# imu_hand.net
KiCad netlist of a schematic drawn in EAGLE
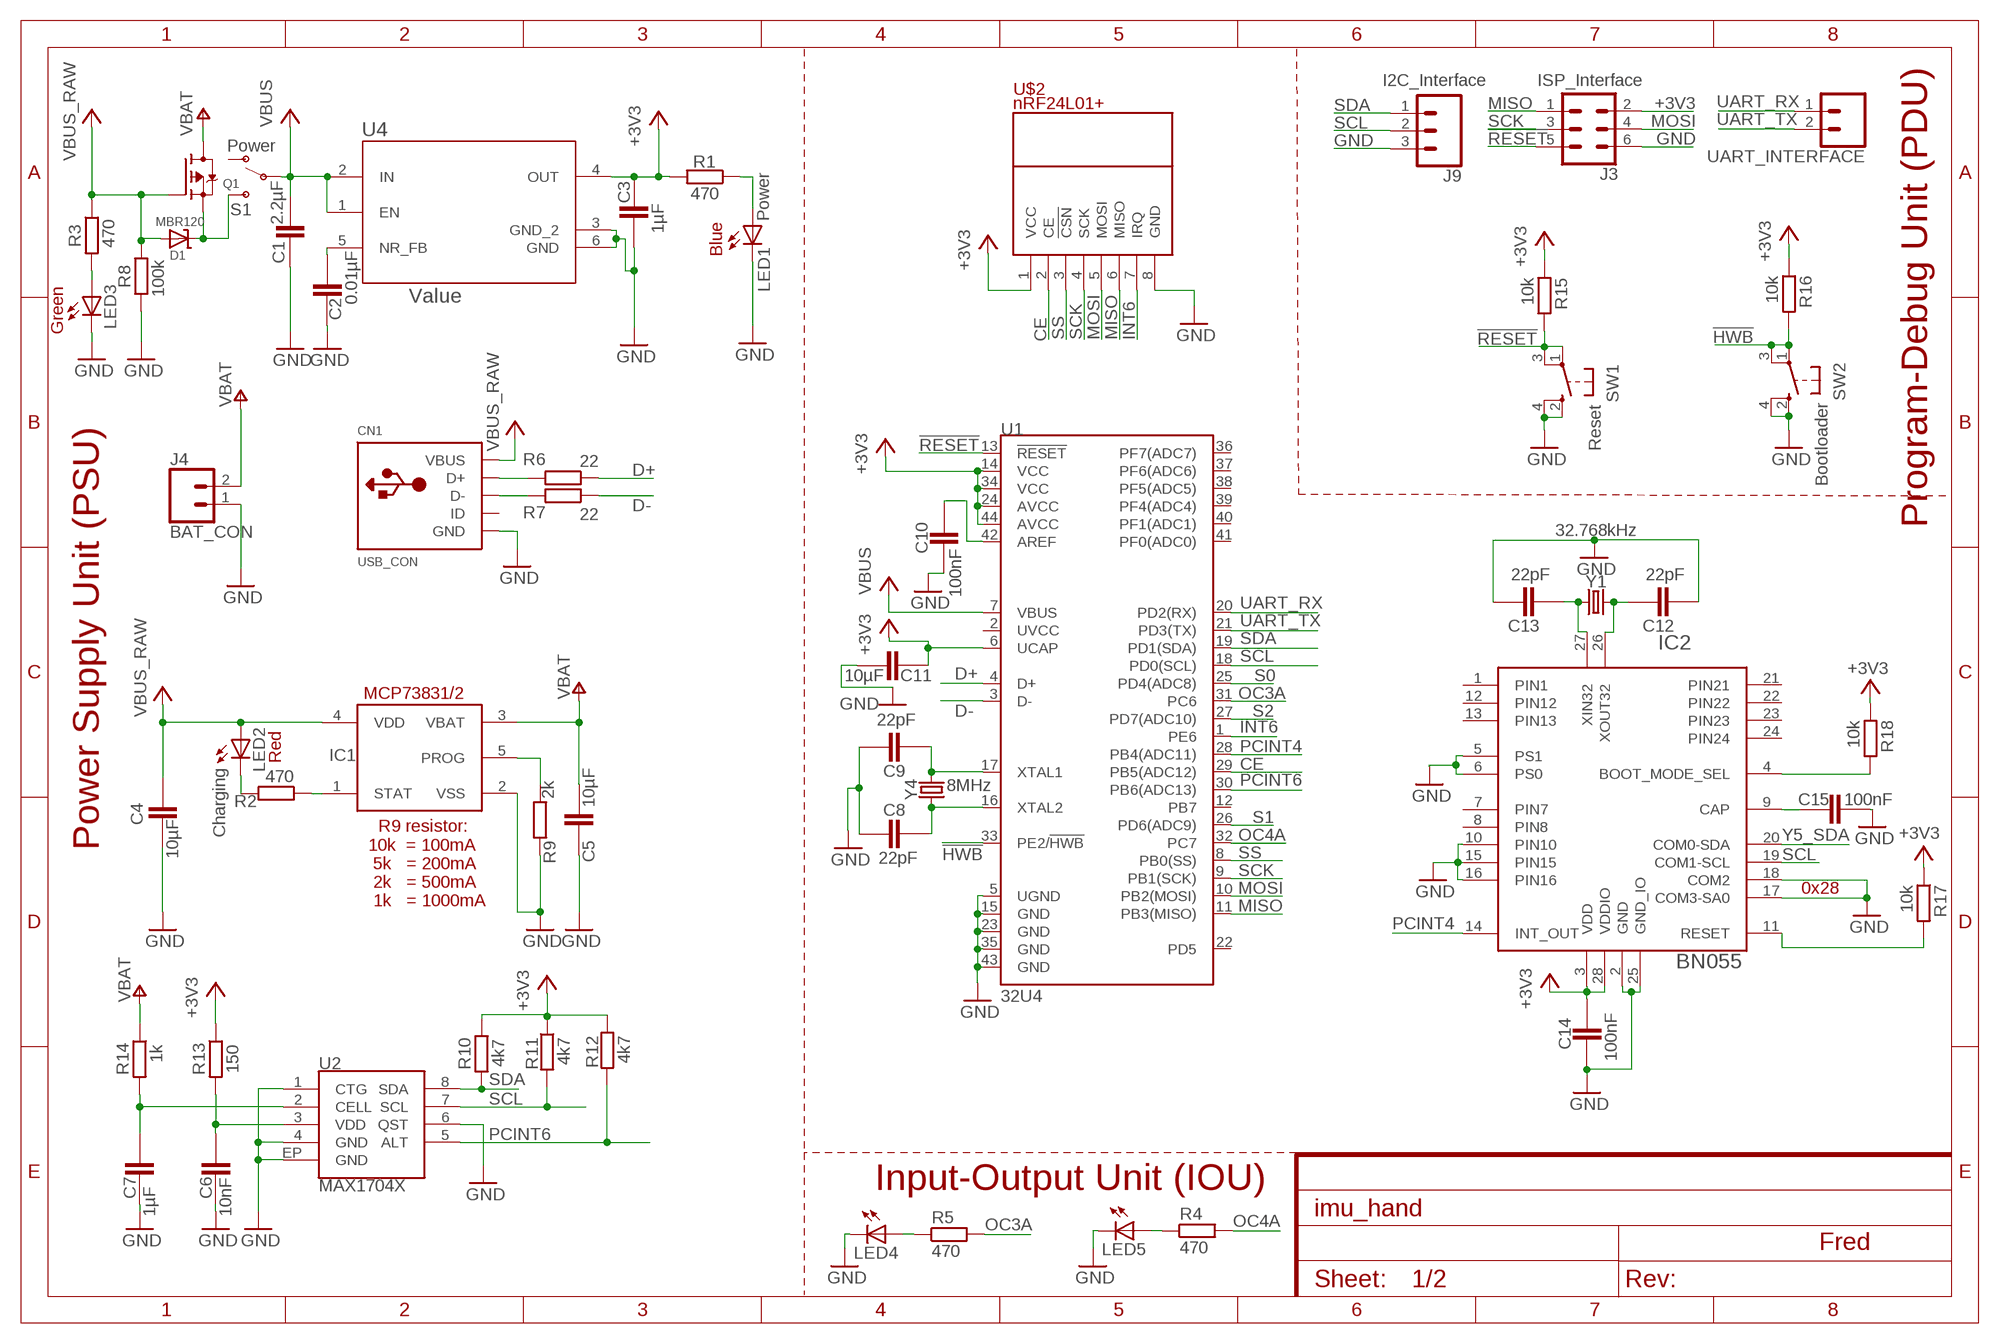
[diagram p0: schematic, sheet 1]
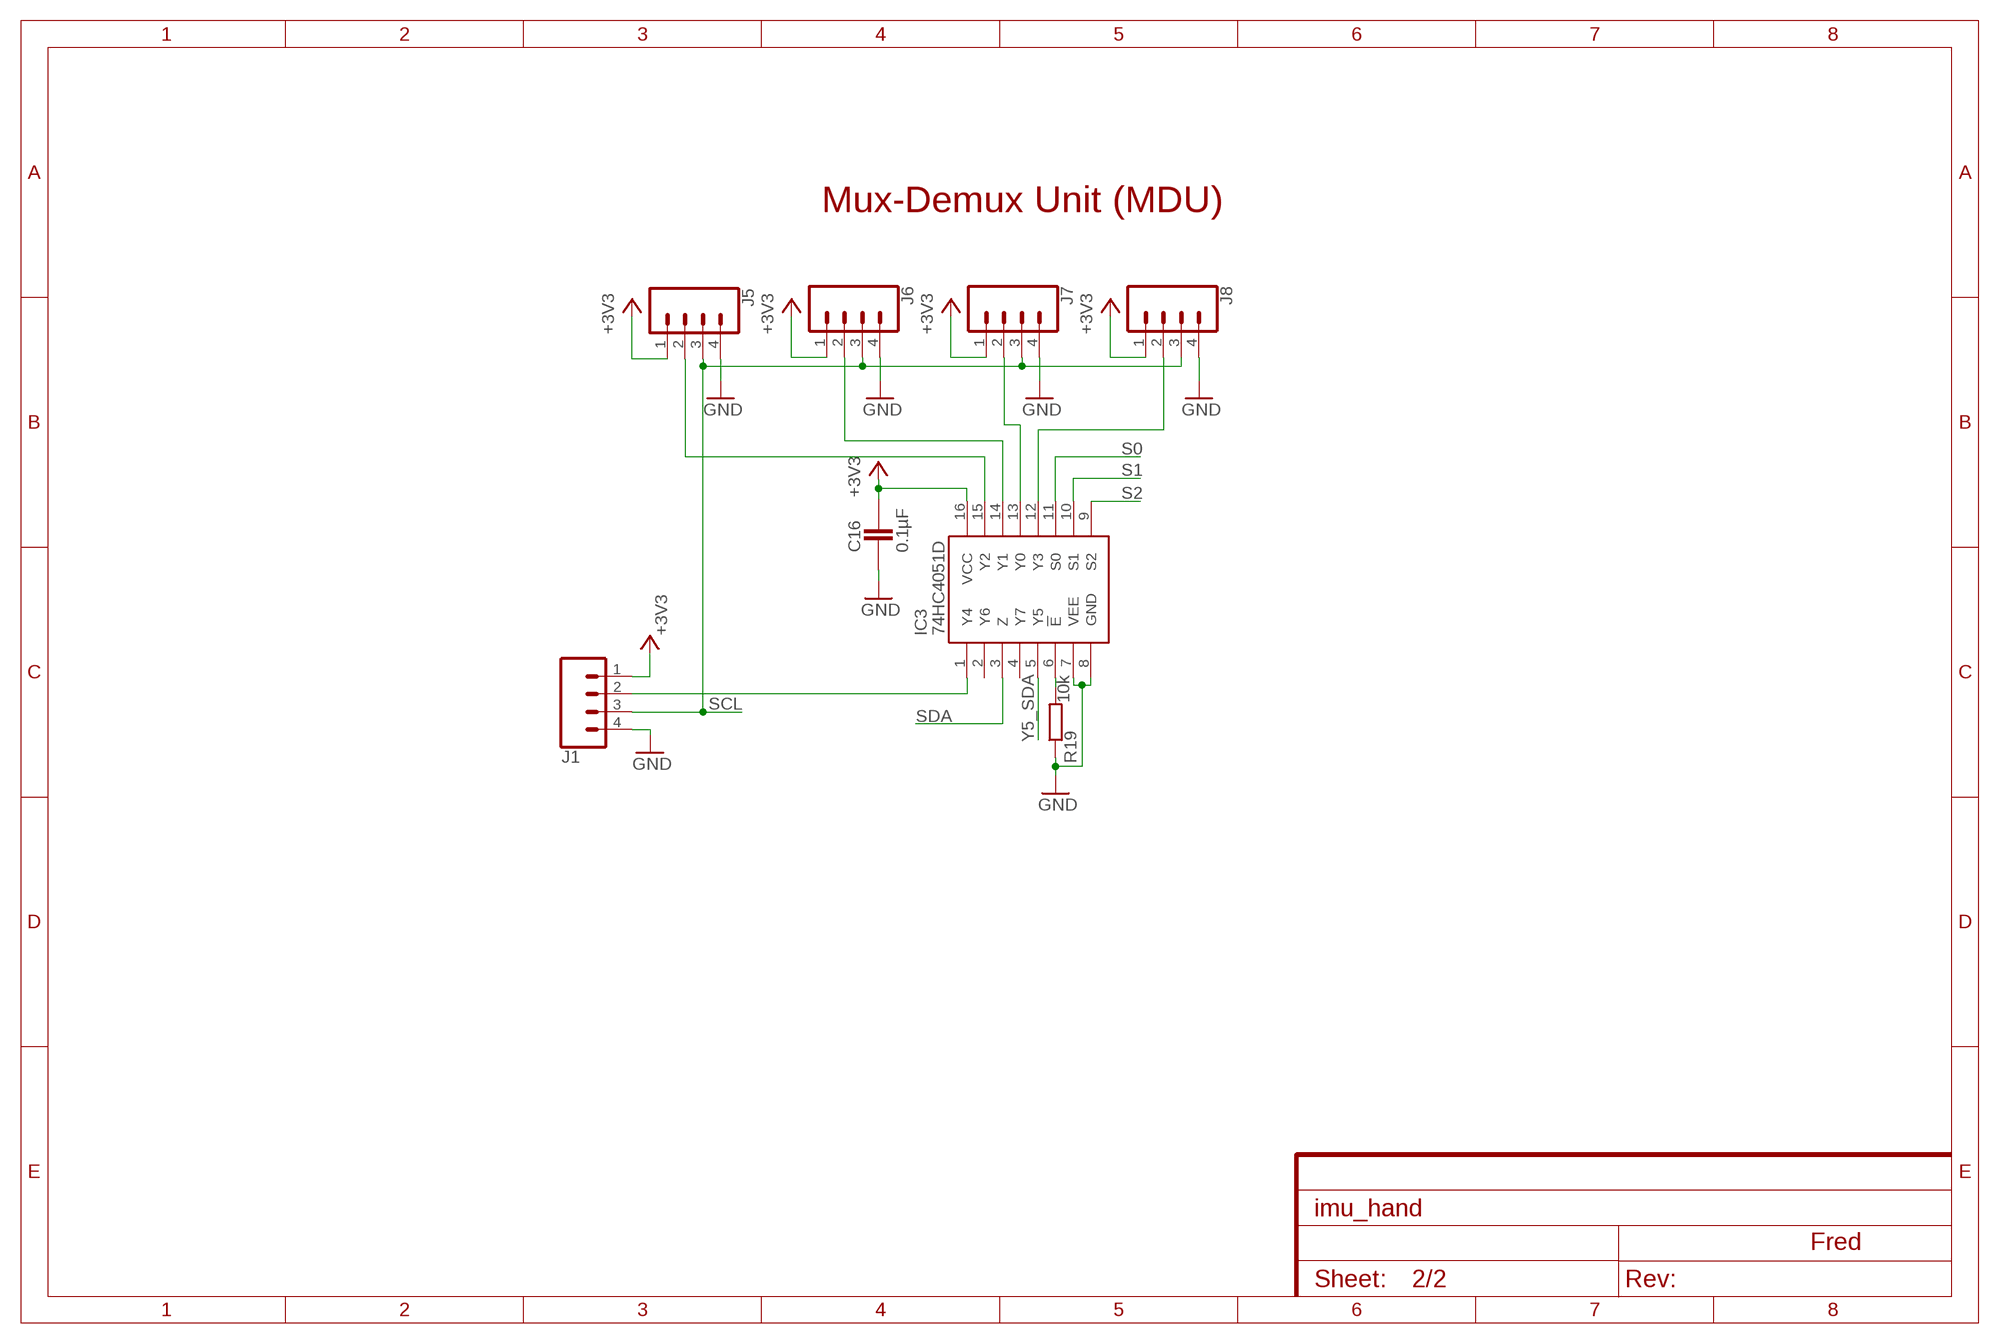
[diagram p1: schematic, sheet 2]

(export (version "E")
  (design (tool "Eeschema 10.0.6"))
  (components
    (comp (ref "C16")
      (value "0.1µF")
      (footprint "eagle-import:CAPC1608X92N")
      (libsource (lib "eagle-import") (part "CAPACITOR_0603"))
    )
    (comp (ref "IC3")
      (value "74HC4051D")
      (footprint "eagle-import:SOIC127P600X175-16N")
      (fields (field (name "RS_PART_NUMBER") "1697756P"))
      (libsource (lib "eagle-import") (part "74HC4051D"))
    )
    (comp (ref "J1")
      (value "CONN_04SMD2")
      (footprint "eagle-import:1X04_1MM_RA")
      (libsource (lib "eagle-import") (part "CONN_04SMD2"))
    )
    (comp (ref "J5")
      (value "CONN_04SMD2")
      (footprint "eagle-import:1X04_1MM_RA")
      (libsource (lib "eagle-import") (part "CONN_04SMD2"))
    )
    (comp (ref "J6")
      (value "CONN_04SMD2")
      (footprint "eagle-import:1X04_1MM_RA")
      (libsource (lib "eagle-import") (part "CONN_04SMD2"))
    )
    (comp (ref "J7")
      (value "CONN_04SMD2")
      (footprint "eagle-import:1X04_1MM_RA")
      (libsource (lib "eagle-import") (part "CONN_04SMD2"))
    )
    (comp (ref "J8")
      (value "CONN_04SMD2")
      (footprint "eagle-import:1X04_1MM_RA")
      (libsource (lib "eagle-import") (part "CONN_04SMD2"))
    )
    (comp (ref "R19")
      (value "10k")
      (footprint "eagle-import:RESC1608X55N")
      (libsource (lib "eagle-import") (part "RESISTOR_0603"))
    )
    (comp (ref "C1")
      (value "2.2µF")
      (footprint "eagle-import:CAPC1608X92N")
      (libsource (lib "eagle-import") (part "CAPACITOR_0603"))
    )
    (comp (ref "C2")
      (value "0.01µF")
      (footprint "eagle-import:CAPC1608X92N")
      (libsource (lib "eagle-import") (part "CAPACITOR_0603"))
    )
    (comp (ref "C3")
      (value "1µF")
      (footprint "eagle-import:CAPC1608X92N")
      (libsource (lib "eagle-import") (part "CAPACITOR_0603"))
    )
    (comp (ref "C4")
      (value "10µF")
      (footprint "eagle-import:CAPC1608X92N")
      (libsource (lib "eagle-import") (part "CAPACITOR_0603"))
    )
    (comp (ref "C5")
      (value "10µF")
      (footprint "eagle-import:CAPC1608X92N")
      (libsource (lib "eagle-import") (part "CAPACITOR_0603"))
    )
    (comp (ref "C6")
      (value "10nF")
      (footprint "eagle-import:CAPC1608X92N")
      (libsource (lib "eagle-import") (part "CAPACITOR_0603"))
    )
    (comp (ref "C7")
      (value "1µF")
      (footprint "eagle-import:CAPC1608X92N")
      (libsource (lib "eagle-import") (part "CAPACITOR_0603"))
    )
    (comp (ref "C8")
      (value "22pF")
      (footprint "eagle-import:CAPC1608X92N")
      (libsource (lib "eagle-import") (part "CAPACITOR_0603"))
    )
    (comp (ref "C9")
      (value "22pF")
      (footprint "eagle-import:CAPC1608X92N")
      (libsource (lib "eagle-import") (part "CAPACITOR_0603"))
    )
    (comp (ref "C10")
      (value "100nF")
      (footprint "eagle-import:CAPC1608X92N")
      (libsource (lib "eagle-import") (part "CAPACITOR_0603"))
    )
    (comp (ref "C11")
      (value "10µF")
      (footprint "eagle-import:CAPC1608X92N")
      (libsource (lib "eagle-import") (part "CAPACITOR_0603"))
    )
    (comp (ref "C12")
      (value "22pF")
      (footprint "eagle-import:CAPC1608X92N")
      (libsource (lib "eagle-import") (part "CAPACITOR_0603"))
    )
    (comp (ref "C13")
      (value "22pF")
      (footprint "eagle-import:CAPC1608X92N")
      (libsource (lib "eagle-import") (part "CAPACITOR_0603"))
    )
    (comp (ref "C14")
      (value "100nF")
      (footprint "eagle-import:CAPC1608X92N")
      (libsource (lib "eagle-import") (part "CAPACITOR_0603"))
    )
    (comp (ref "C15")
      (value "100nF")
      (footprint "eagle-import:CAPC1608X92N")
      (libsource (lib "eagle-import") (part "CAPACITOR_0603"))
    )
    (comp (ref "CN1")
      (value "USB_CON")
      (footprint "eagle-import:USB-MINIB")
      (libsource (lib "eagle-import") (part "USBMINIB"))
    )
    (comp (ref "D1")
      (value "MBR120")
      (footprint "eagle-import:SOD-123FL")
      (libsource (lib "eagle-import") (part "DIODE_SOD-123FL"))
    )
    (comp (ref "IC1")
      (value "MCP73831/OT")
      (footprint "eagle-import:SOT23-5L")
      (libsource (lib "eagle-import") (part "MCP73831/OT"))
    )
    (comp (ref "IC2")
      (value "BN055")
      (footprint "eagle-import:LGA-28_3.80X5.20_0.5")
      (fields (field (name "PART_NUMBER") "BNO055"))
      (libsource (lib "eagle-import") (part "1658_BNO055"))
    )
    (comp (ref "J3")
      (value "ISP_Interface")
      (footprint "eagle-import:2X3")
      (libsource (lib "eagle-import") (part "CONN_03X2FEMALE"))
    )
    (comp (ref "J4")
      (value "BAT_CON")
      (footprint "eagle-import:1X02")
      (libsource (lib "eagle-import") (part "CONN_02"))
    )
    (comp (ref "J9")
      (value "I2C_Interface")
      (footprint "eagle-import:1X03")
      (libsource (lib "eagle-import") (part "CONN_03"))
    )
    (comp (ref "LED1")
      (value "Power")
      (footprint "eagle-import:CHIPLED_0603")
      (libsource (lib "eagle-import") (part "LEDCHIPLED_0603"))
    )
    (comp (ref "LED2")
      (value "Charging")
      (footprint "eagle-import:CHIPLED_0603")
      (libsource (lib "eagle-import") (part "LEDCHIPLED_0603"))
    )
    (comp (ref "LED3")
      (value "Done")
      (footprint "eagle-import:CHIPLED_0603")
      (libsource (lib "eagle-import") (part "LEDCHIPLED_0603"))
    )
    (comp (ref "LED4")
      (value "LEDCHIPLED_0603")
      (footprint "eagle-import:CHIPLED_0603")
      (libsource (lib "eagle-import") (part "LEDCHIPLED_0603"))
    )
    (comp (ref "LED5")
      (value "LEDCHIPLED_0603")
      (footprint "eagle-import:CHIPLED_0603")
      (libsource (lib "eagle-import") (part "LEDCHIPLED_0603"))
    )
    (comp (ref "Q1")
      (value "MICROBUILDER_MOSFET-P")
      (footprint "eagle-import:MICROBUILDER_SOT23-R")
      (libsource (lib "eagle-import") (part "MICROBUILDER_MOSFET-P"))
    )
    (comp (ref "R1")
      (value "470")
      (footprint "eagle-import:RESC1608X55N")
      (libsource (lib "eagle-import") (part "RESISTOR_0603"))
    )
    (comp (ref "R2")
      (value "470")
      (footprint "eagle-import:RESC1608X55N")
      (libsource (lib "eagle-import") (part "RESISTOR_0603"))
    )
    (comp (ref "R3")
      (value "470")
      (footprint "eagle-import:RESC1608X55N")
      (libsource (lib "eagle-import") (part "RESISTOR_0603"))
    )
    (comp (ref "R4")
      (value "470")
      (footprint "eagle-import:RESC1608X55N")
      (libsource (lib "eagle-import") (part "RESISTOR_0603"))
    )
    (comp (ref "R5")
      (value "470")
      (footprint "eagle-import:RESC1608X55N")
      (libsource (lib "eagle-import") (part "RESISTOR_0603"))
    )
    (comp (ref "R6")
      (value "22")
      (footprint "eagle-import:RESC1608X55N")
      (libsource (lib "eagle-import") (part "RESISTOR_0603"))
    )
    (comp (ref "R7")
      (value "22")
      (footprint "eagle-import:RESC1608X55N")
      (libsource (lib "eagle-import") (part "RESISTOR_0603"))
    )
    (comp (ref "R8")
      (value "100k")
      (footprint "eagle-import:RESC1608X55N")
      (libsource (lib "eagle-import") (part "RESISTOR_0603"))
    )
    (comp (ref "R9")
      (value "2k")
      (footprint "eagle-import:RESC1608X55N")
      (libsource (lib "eagle-import") (part "RESISTOR_0603"))
    )
    (comp (ref "R10")
      (value "4k7")
      (footprint "eagle-import:RESC1608X55N")
      (libsource (lib "eagle-import") (part "RESISTOR_0603"))
    )
    (comp (ref "R11")
      (value "4k7")
      (footprint "eagle-import:RESC1608X55N")
      (libsource (lib "eagle-import") (part "RESISTOR_0603"))
    )
    (comp (ref "R12")
      (value "4k7")
      (footprint "eagle-import:RESC1608X55N")
      (libsource (lib "eagle-import") (part "RESISTOR_0603"))
    )
    (comp (ref "R13")
      (value "150")
      (footprint "eagle-import:RESC1608X55N")
      (libsource (lib "eagle-import") (part "RESISTOR_0603"))
    )
    (comp (ref "R14")
      (value "1k")
      (footprint "eagle-import:RESC1608X55N")
      (libsource (lib "eagle-import") (part "RESISTOR_0603"))
    )
    (comp (ref "R15")
      (value "10k")
      (footprint "eagle-import:RESC1608X55N")
      (libsource (lib "eagle-import") (part "RESISTOR_0603"))
    )
    (comp (ref "R16")
      (value "10k")
      (footprint "eagle-import:RESC1608X55N")
      (libsource (lib "eagle-import") (part "RESISTOR_0603"))
    )
    (comp (ref "R17")
      (value "10k")
      (footprint "eagle-import:RESC1608X55N")
      (libsource (lib "eagle-import") (part "RESISTOR_0603"))
    )
    (comp (ref "R18")
      (value "10k")
      (footprint "eagle-import:RESC1608X55N")
      (libsource (lib "eagle-import") (part "RESISTOR_0603"))
    )
    (comp (ref "S1")
      (value "Power")
      (footprint "eagle-import:SWITCH_SPDT_PTH_11.6X4.0MM")
      (libsource (lib "eagle-import") (part "SWITCH-SPDT-PTH-11.6X4.0MM"))
    )
    (comp (ref "SW1")
      (value "Reset")
      (footprint "eagle-import:KMR2")
      (libsource (lib "eagle-import") (part "SPST_TACT-KMR2"))
    )
    (comp (ref "SW2")
      (value "Bootloader")
      (footprint "eagle-import:KMR2")
      (libsource (lib "eagle-import") (part "SPST_TACT-KMR2"))
    )
    (comp (ref "U$2")
      (value "nRF24L01+")
      (footprint "eagle-import:6-PIN-BREAKOUT")
      (libsource (lib "eagle-import") (part "6-PIN-BREAKOUT6-PIN-BREAKOUT"))
    )
    (comp (ref "U1")
      (value "32U4")
      (footprint "eagle-import:TQFP44")
      (libsource (lib "eagle-import") (part "ATMEGA32U4TQFP-44"))
    )
    (comp (ref "U2")
      (value "MAX1704X")
      (footprint "eagle-import:TDFN-8")
      (libsource (lib "eagle-import") (part "MAX1704X"))
    )
    (comp (ref "U4")
      (value "Value")
      (footprint "eagle-import:DCQ0006A_N")
      (fields (field (name "MANUFACTURER") "Texas Instruments") (field (name "PARTNUMBER") "TPS79633QDCQRQ1"))
      (libsource (lib "eagle-import") (part "TPS79633QDCQRQ1"))
    )
    (comp (ref "UART_INTERFACE")
      (value "UART_Interface")
      (footprint "eagle-import:1X02")
      (libsource (lib "eagle-import") (part "CONN_02"))
    )
    (comp (ref "Y1")
      (value "32.768kHz")
      (footprint "eagle-import:CRYSTAL-SMD-3.2X1.5MM")
      (libsource (lib "eagle-import") (part "CRYSTAL-32.768KHZSMD-3.2X1.5"))
    )
    (comp (ref "Y4")
      (value "8MHz")
      (footprint "eagle-import:CRYSTAL-SMD-5X3.2-4PAD")
      (libsource (lib "eagle-import") (part "CRYSTAL-8MHZSMD-5X3.2"))
    )
  )
  (nets
    (net (code "1") (name "+3V3") (class "Default")
      (node (ref "C11") (pin "1") (pinfunction "1_1") (pintype "passive"))
      (node (ref "C14") (pin "1") (pinfunction "1_1") (pintype "passive"))
      (node (ref "C16") (pin "2") (pinfunction "2_2") (pintype "passive"))
      (node (ref "C3") (pin "2") (pinfunction "2_2") (pintype "passive"))
      (node (ref "IC2") (pin "28") (pinfunction "VDDIO_28") (pintype "power_in"))
      (node (ref "IC2") (pin "3") (pinfunction "VDD_3") (pintype "power_in"))
      (node (ref "IC3") (pin "16") (pinfunction "VCC_16") (pintype "bidirectional"))
      (node (ref "J1") (pin "1") (pinfunction "1_1") (pintype "passive"))
      (node (ref "J3") (pin "2") (pinfunction "2_2") (pintype "bidirectional"))
      (node (ref "J5") (pin "1") (pinfunction "1_1") (pintype "passive"))
      (node (ref "J6") (pin "1") (pinfunction "1_1") (pintype "passive"))
      (node (ref "J7") (pin "1") (pinfunction "1_1") (pintype "passive"))
      (node (ref "J8") (pin "1") (pinfunction "1_1") (pintype "passive"))
      (node (ref "R1") (pin "2") (pinfunction "2_2") (pintype "passive"))
      (node (ref "R10") (pin "1") (pinfunction "1_1") (pintype "passive"))
      (node (ref "R11") (pin "1") (pinfunction "1_1") (pintype "passive"))
      (node (ref "R12") (pin "1") (pinfunction "1_1") (pintype "passive"))
      (node (ref "R13") (pin "1") (pinfunction "1_1") (pintype "passive"))
      (node (ref "R15") (pin "1") (pinfunction "1_1") (pintype "passive"))
      (node (ref "R16") (pin "1") (pinfunction "1_1") (pintype "passive"))
      (node (ref "R17") (pin "1") (pinfunction "1_1") (pintype "passive"))
      (node (ref "R18") (pin "1") (pinfunction "1_1") (pintype "passive"))
      (node (ref "U$2") (pin "1") (pinfunction "VCC_1") (pintype "bidirectional"))
      (node (ref "U1") (pin "14") (pinfunction "VCC_14") (pintype "bidirectional"))
      (node (ref "U1") (pin "24") (pinfunction "AVCC_24") (pintype "bidirectional"))
      (node (ref "U1") (pin "34") (pinfunction "VCC_34") (pintype "bidirectional"))
      (node (ref "U1") (pin "44") (pinfunction "AVCC_44") (pintype "bidirectional"))
      (node (ref "U1") (pin "6") (pinfunction "UCAP_6") (pintype "bidirectional"))
      (node (ref "U4") (pin "4") (pinfunction "OUT_4") (pintype "power_in"))
    )
    (net (code "2") (name "CE") (class "Default")
      (node (ref "U$2") (pin "2") (pinfunction "CE_2") (pintype "bidirectional"))
      (node (ref "U1") (pin "29") (pinfunction "PB5(ADC12)_29") (pintype "bidirectional"))
    )
    (net (code "3") (name "D+") (class "Default")
      (node (ref "R6") (pin "1") (pinfunction "1_1") (pintype "passive"))
      (node (ref "U1") (pin "4") (pinfunction "D+_4") (pintype "bidirectional"))
    )
    (net (code "4") (name "D-") (class "Default")
      (node (ref "R7") (pin "1") (pinfunction "1_1") (pintype "passive"))
      (node (ref "U1") (pin "3") (pinfunction "D-_3") (pintype "bidirectional"))
    )
    (net (code "5") (name "GND") (class "Default")
      (node (ref "C1") (pin "1") (pinfunction "1_1") (pintype "passive"))
      (node (ref "C10") (pin "2") (pinfunction "2_2") (pintype "passive"))
      (node (ref "C11") (pin "2") (pinfunction "2_2") (pintype "passive"))
      (node (ref "C12") (pin "1") (pinfunction "1_1") (pintype "passive"))
      (node (ref "C13") (pin "2") (pinfunction "2_2") (pintype "passive"))
      (node (ref "C14") (pin "2") (pinfunction "2_2") (pintype "passive"))
      (node (ref "C15") (pin "2") (pinfunction "2_2") (pintype "passive"))
      (node (ref "C16") (pin "1") (pinfunction "1_1") (pintype "passive"))
      (node (ref "C2") (pin "1") (pinfunction "1_1") (pintype "passive"))
      (node (ref "C3") (pin "1") (pinfunction "1_1") (pintype "passive"))
      (node (ref "C4") (pin "1") (pinfunction "1_1") (pintype "passive"))
      (node (ref "C5") (pin "1") (pinfunction "1_1") (pintype "passive"))
      (node (ref "C6") (pin "1") (pinfunction "1_1") (pintype "passive"))
      (node (ref "C7") (pin "1") (pinfunction "1_1") (pintype "passive"))
      (node (ref "C8") (pin "2") (pinfunction "2_2") (pintype "passive"))
      (node (ref "C9") (pin "2") (pinfunction "2_2") (pintype "passive"))
      (node (ref "CN1") (pin "GND") (pinfunction "GND_GND") (pintype "power_in"))
      (node (ref "IC1") (pin "2") (pinfunction "VSS_2") (pintype "power_in"))
      (node (ref "IC2") (pin "10") (pinfunction "PIN10_10") (pintype "passive"))
      (node (ref "IC2") (pin "15") (pinfunction "PIN15_15") (pintype "passive"))
      (node (ref "IC2") (pin "16") (pinfunction "PIN16_16") (pintype "passive"))
      (node (ref "IC2") (pin "17") (pinfunction "COM3-SA0_17") (pintype "bidirectional"))
      (node (ref "IC2") (pin "18") (pinfunction "COM2_18") (pintype "bidirectional"))
      (node (ref "IC2") (pin "2") (pinfunction "GND_2") (pintype "power_in"))
      (node (ref "IC2") (pin "25") (pinfunction "GND_IO_25") (pintype "power_in"))
      (node (ref "IC2") (pin "5") (pinfunction "PS1_5") (pintype "input"))
      (node (ref "IC2") (pin "6") (pinfunction "PS0_6") (pintype "input"))
      (node (ref "IC3") (pin "7") (pinfunction "VEE_7") (pintype "bidirectional"))
      (node (ref "IC3") (pin "8") (pinfunction "GND_8") (pintype "bidirectional"))
      (node (ref "J1") (pin "4") (pinfunction "4_4") (pintype "passive"))
      (node (ref "J3") (pin "6") (pinfunction "6_6") (pintype "bidirectional"))
      (node (ref "J4") (pin "1") (pinfunction "1_1") (pintype "passive"))
      (node (ref "J5") (pin "4") (pinfunction "4_4") (pintype "passive"))
      (node (ref "J6") (pin "4") (pinfunction "4_4") (pintype "passive"))
      (node (ref "J7") (pin "4") (pinfunction "4_4") (pintype "passive"))
      (node (ref "J8") (pin "4") (pinfunction "4_4") (pintype "passive"))
      (node (ref "J9") (pin "3") (pinfunction "3_3") (pintype "passive"))
      (node (ref "LED1") (pin "C") (pinfunction "C_C") (pintype "passive"))
      (node (ref "LED3") (pin "C") (pinfunction "C_C") (pintype "passive"))
      (node (ref "LED4") (pin "C") (pinfunction "C_C") (pintype "passive"))
      (node (ref "LED5") (pin "C") (pinfunction "C_C") (pintype "passive"))
      (node (ref "R19") (pin "1") (pinfunction "1_1") (pintype "passive"))
      (node (ref "R8") (pin "2") (pinfunction "2_2") (pintype "passive"))
      (node (ref "R9") (pin "2") (pinfunction "2_2") (pintype "passive"))
      (node (ref "SW1") (pin "2") (pinfunction "S_2") (pintype "passive"))
      (node (ref "SW1") (pin "4") (pinfunction "S1_4") (pintype "passive"))
      (node (ref "SW2") (pin "2") (pinfunction "S_2") (pintype "passive"))
      (node (ref "SW2") (pin "4") (pinfunction "S1_4") (pintype "passive"))
      (node (ref "U$2") (pin "8") (pinfunction "GND_8") (pintype "bidirectional"))
      (node (ref "U1") (pin "15") (pinfunction "GND_15") (pintype "bidirectional"))
      (node (ref "U1") (pin "23") (pinfunction "GND_23") (pintype "bidirectional"))
      (node (ref "U1") (pin "35") (pinfunction "GND_35") (pintype "bidirectional"))
      (node (ref "U1") (pin "43") (pinfunction "GND_43") (pintype "bidirectional"))
      (node (ref "U1") (pin "5") (pinfunction "UGND_5") (pintype "bidirectional"))
      (node (ref "U2") (pin "1") (pinfunction "CTG_1") (pintype "bidirectional"))
      (node (ref "U2") (pin "4") (pinfunction "GND_4") (pintype "bidirectional"))
      (node (ref "U2") (pin "6") (pinfunction "QST_6") (pintype "bidirectional"))
      (node (ref "U2") (pin "EP") (pinfunction "GND_EP") (pintype "bidirectional"))
      (node (ref "U4") (pin "3") (pinfunction "GND_2_3") (pintype "power_in"))
      (node (ref "U4") (pin "6") (pinfunction "GND_6") (pintype "power_in"))
    )
    (net (code "6") (name "INT6") (class "Default")
      (node (ref "U$2") (pin "7") (pinfunction "IRQ_7") (pintype "bidirectional"))
      (node (ref "U1") (pin "1") (pinfunction "PE6_1") (pintype "bidirectional"))
    )
    (net (code "7") (name "MISO") (class "Default")
      (node (ref "J3") (pin "1") (pinfunction "1_1") (pintype "bidirectional"))
      (node (ref "U$2") (pin "6") (pinfunction "MISO_6") (pintype "bidirectional"))
      (node (ref "U1") (pin "11") (pinfunction "PB3(MISO)_11") (pintype "bidirectional"))
    )
    (net (code "8") (name "MOSI") (class "Default")
      (node (ref "J3") (pin "4") (pinfunction "4_4") (pintype "bidirectional"))
      (node (ref "U$2") (pin "5") (pinfunction "MOSI_5") (pintype "bidirectional"))
      (node (ref "U1") (pin "10") (pinfunction "PB2(MOSI)_10") (pintype "bidirectional"))
    )
    (net (code "9") (name "Net-(CN1-PadD+)") (class "Default")
      (node (ref "CN1") (pin "D+") (pinfunction "D+_D+") (pintype "bidirectional"))
      (node (ref "R6") (pin "2") (pinfunction "2_2") (pintype "passive"))
    )
    (net (code "10") (name "Net-(CN1-PadD-)") (class "Default")
      (node (ref "CN1") (pin "D-") (pinfunction "D-_D-") (pintype "bidirectional"))
      (node (ref "R7") (pin "2") (pinfunction "2_2") (pintype "passive"))
    )
    (net (code "11") (name "Net-(IC1-PROG)") (class "Default")
      (node (ref "IC1") (pin "5") (pinfunction "PROG_5") (pintype "input"))
      (node (ref "R9") (pin "1") (pinfunction "1_1") (pintype "passive"))
    )
    (net (code "12") (name "Net-(IC1-STAT)") (class "Default")
      (node (ref "IC1") (pin "1") (pinfunction "STAT_1") (pintype "output"))
      (node (ref "R2") (pin "1") (pinfunction "1_1") (pintype "passive"))
    )
    (net (code "13") (name "Net-(IC2-BOOT_MODE_SEL)") (class "Default")
      (node (ref "IC2") (pin "4") (pinfunction "BOOT_MODE_SEL_4") (pintype "input"))
      (node (ref "R18") (pin "2") (pinfunction "2_2") (pintype "passive"))
    )
    (net (code "14") (name "Net-(IC2-CAP)") (class "Default")
      (node (ref "C15") (pin "1") (pinfunction "1_1") (pintype "passive"))
      (node (ref "IC2") (pin "9") (pinfunction "CAP_9") (pintype "tri_state"))
    )
    (net (code "15") (name "Net-(IC2-RESET)") (class "Default")
      (node (ref "IC2") (pin "11") (pinfunction "RESET_11") (pintype "input"))
      (node (ref "R17") (pin "2") (pinfunction "2_2") (pintype "passive"))
    )
    (net (code "16") (name "Net-(IC2-XIN32)") (class "Default")
      (node (ref "C13") (pin "1") (pinfunction "1_1") (pintype "passive"))
      (node (ref "IC2") (pin "27") (pinfunction "XIN32_27") (pintype "bidirectional"))
      (node (ref "Y1") (pin "P$1") (pinfunction "1_P$1") (pintype "passive"))
    )
    (net (code "17") (name "Net-(IC2-XOUT32)") (class "Default")
      (node (ref "C12") (pin "2") (pinfunction "2_2") (pintype "passive"))
      (node (ref "IC2") (pin "26") (pinfunction "XOUT32_26") (pintype "output"))
      (node (ref "Y1") (pin "P$2") (pinfunction "2_P$2") (pintype "passive"))
    )
    (net (code "18") (name "Net-(IC3-Y0)") (class "Default")
      (node (ref "IC3") (pin "13") (pinfunction "Y0_13") (pintype "bidirectional"))
      (node (ref "J7") (pin "2") (pinfunction "2_2") (pintype "passive"))
    )
    (net (code "19") (name "Net-(IC3-Y1)") (class "Default")
      (node (ref "IC3") (pin "14") (pinfunction "Y1_14") (pintype "bidirectional"))
      (node (ref "J6") (pin "2") (pinfunction "2_2") (pintype "passive"))
    )
    (net (code "20") (name "Net-(IC3-Y2)") (class "Default")
      (node (ref "IC3") (pin "15") (pinfunction "Y2_15") (pintype "bidirectional"))
      (node (ref "J5") (pin "2") (pinfunction "2_2") (pintype "passive"))
    )
    (net (code "21") (name "Net-(IC3-Y3)") (class "Default")
      (node (ref "IC3") (pin "12") (pinfunction "Y3_12") (pintype "bidirectional"))
      (node (ref "J8") (pin "2") (pinfunction "2_2") (pintype "passive"))
    )
    (net (code "22") (name "Net-(IC3-Y4)") (class "Default")
      (node (ref "IC3") (pin "1") (pinfunction "Y4_1") (pintype "bidirectional"))
      (node (ref "J1") (pin "2") (pinfunction "2_2") (pintype "passive"))
    )
    (net (code "23") (name "Net-(IC3-~{E})") (class "Default")
      (node (ref "IC3") (pin "6") (pinfunction "~{E}_6") (pintype "bidirectional"))
      (node (ref "R19") (pin "2") (pinfunction "2_2") (pintype "passive"))
    )
    (net (code "24") (name "Net-(LED1-PadA)") (class "Default")
      (node (ref "LED1") (pin "A") (pinfunction "A_A") (pintype "passive"))
      (node (ref "R1") (pin "1") (pinfunction "1_1") (pintype "passive"))
    )
    (net (code "25") (name "Net-(LED2-PadC)") (class "Default")
      (node (ref "LED2") (pin "C") (pinfunction "C_C") (pintype "passive"))
      (node (ref "R2") (pin "2") (pinfunction "2_2") (pintype "passive"))
    )
    (net (code "26") (name "Net-(LED3-PadA)") (class "Default")
      (node (ref "LED3") (pin "A") (pinfunction "A_A") (pintype "passive"))
      (node (ref "R3") (pin "2") (pinfunction "2_2") (pintype "passive"))
    )
    (net (code "27") (name "Net-(LED4-PadA)") (class "Default")
      (node (ref "LED4") (pin "A") (pinfunction "A_A") (pintype "passive"))
      (node (ref "R5") (pin "1") (pinfunction "1_1") (pintype "passive"))
    )
    (net (code "28") (name "Net-(LED5-PadA)") (class "Default")
      (node (ref "LED5") (pin "A") (pinfunction "A_A") (pintype "passive"))
      (node (ref "R4") (pin "1") (pinfunction "1_1") (pintype "passive"))
    )
    (net (code "29") (name "Net-(Q1-S)") (class "Default")
      (node (ref "D1") (pin "C") (pinfunction "C_C") (pintype "passive"))
      (node (ref "Q1") (pin "2") (pinfunction "S_2") (pintype "passive"))
      (node (ref "S1") (pin "3") (pinfunction "S_3") (pintype "passive"))
    )
    (net (code "30") (name "Net-(U1-AREF)") (class "Default")
      (node (ref "C10") (pin "1") (pinfunction "1_1") (pintype "passive"))
      (node (ref "U1") (pin "42") (pinfunction "AREF_42") (pintype "bidirectional"))
    )
    (net (code "31") (name "Net-(U1-XTAL1)") (class "Default")
      (node (ref "C9") (pin "1") (pinfunction "1_1") (pintype "passive"))
      (node (ref "U1") (pin "17") (pinfunction "XTAL1_17") (pintype "bidirectional"))
      (node (ref "Y4") (pin "3") (pinfunction "2_3") (pintype "passive"))
    )
    (net (code "32") (name "Net-(U1-XTAL2)") (class "Default")
      (node (ref "C8") (pin "1") (pinfunction "1_1") (pintype "passive"))
      (node (ref "U1") (pin "16") (pinfunction "XTAL2_16") (pintype "bidirectional"))
      (node (ref "Y4") (pin "1") (pinfunction "1_1") (pintype "passive"))
    )
    (net (code "33") (name "Net-(U2-CELL)") (class "Default")
      (node (ref "C7") (pin "2") (pinfunction "2_2") (pintype "passive"))
      (node (ref "R14") (pin "2") (pinfunction "2_2") (pintype "passive"))
      (node (ref "U2") (pin "2") (pinfunction "CELL_2") (pintype "bidirectional"))
    )
    (net (code "34") (name "Net-(U2-VDD)") (class "Default")
      (node (ref "C6") (pin "2") (pinfunction "2_2") (pintype "passive"))
      (node (ref "R13") (pin "2") (pinfunction "2_2") (pintype "passive"))
      (node (ref "U2") (pin "3") (pinfunction "VDD_3") (pintype "bidirectional"))
    )
    (net (code "35") (name "Net-(U4-NR_FB)") (class "Default")
      (node (ref "C2") (pin "2") (pinfunction "2_2") (pintype "passive"))
      (node (ref "U4") (pin "5") (pinfunction "NR_FB_5") (pintype "passive"))
    )
    (net (code "36") (name "OC3A") (class "Default")
      (node (ref "R5") (pin "2") (pinfunction "2_2") (pintype "passive"))
      (node (ref "U1") (pin "31") (pinfunction "PC6_31") (pintype "bidirectional"))
    )
    (net (code "37") (name "OC4A") (class "Default")
      (node (ref "R4") (pin "2") (pinfunction "2_2") (pintype "passive"))
      (node (ref "U1") (pin "32") (pinfunction "PC7_32") (pintype "bidirectional"))
    )
    (net (code "38") (name "PCINT4") (class "Default")
      (node (ref "IC2") (pin "14") (pinfunction "INT_OUT_14") (pintype "output"))
      (node (ref "U1") (pin "28") (pinfunction "PB4(ADC11)_28") (pintype "bidirectional"))
    )
    (net (code "39") (name "PCINT6") (class "Default")
      (node (ref "R12") (pin "2") (pinfunction "2_2") (pintype "passive"))
      (node (ref "U1") (pin "30") (pinfunction "PB6(ADC13)_30") (pintype "bidirectional"))
      (node (ref "U2") (pin "5") (pinfunction "ALT_5") (pintype "bidirectional"))
    )
    (net (code "40") (name "S0") (class "Default")
      (node (ref "IC3") (pin "11") (pinfunction "S0_11") (pintype "bidirectional"))
      (node (ref "U1") (pin "25") (pinfunction "PD4(ADC8)_25") (pintype "bidirectional"))
    )
    (net (code "41") (name "S1") (class "Default")
      (node (ref "IC3") (pin "10") (pinfunction "S1_10") (pintype "bidirectional"))
      (node (ref "U1") (pin "26") (pinfunction "PD6(ADC9)_26") (pintype "bidirectional"))
    )
    (net (code "42") (name "S2") (class "Default")
      (node (ref "IC3") (pin "9") (pinfunction "S2_9") (pintype "bidirectional"))
      (node (ref "U1") (pin "27") (pinfunction "PD7(ADC10)_27") (pintype "bidirectional"))
    )
    (net (code "43") (name "SCK") (class "Default")
      (node (ref "J3") (pin "3") (pinfunction "3_3") (pintype "bidirectional"))
      (node (ref "U$2") (pin "4") (pinfunction "SCK_4") (pintype "bidirectional"))
      (node (ref "U1") (pin "9") (pinfunction "PB1(SCK)_9") (pintype "bidirectional"))
    )
    (net (code "44") (name "SCL") (class "Default")
      (node (ref "IC2") (pin "19") (pinfunction "COM1-SCL_19") (pintype "bidirectional"))
      (node (ref "J1") (pin "3") (pinfunction "3_3") (pintype "passive"))
      (node (ref "J5") (pin "3") (pinfunction "3_3") (pintype "passive"))
      (node (ref "J6") (pin "3") (pinfunction "3_3") (pintype "passive"))
      (node (ref "J7") (pin "3") (pinfunction "3_3") (pintype "passive"))
      (node (ref "J8") (pin "3") (pinfunction "3_3") (pintype "passive"))
      (node (ref "J9") (pin "2") (pinfunction "2_2") (pintype "passive"))
      (node (ref "R11") (pin "2") (pinfunction "2_2") (pintype "passive"))
      (node (ref "U1") (pin "18") (pinfunction "PD0(SCL)_18") (pintype "bidirectional"))
      (node (ref "U2") (pin "7") (pinfunction "SCL_7") (pintype "bidirectional"))
    )
    (net (code "45") (name "SDA") (class "Default")
      (node (ref "IC3") (pin "3") (pinfunction "Z_3") (pintype "bidirectional"))
      (node (ref "J9") (pin "1") (pinfunction "1_1") (pintype "passive"))
      (node (ref "R10") (pin "2") (pinfunction "2_2") (pintype "passive"))
      (node (ref "U1") (pin "19") (pinfunction "PD1(SDA)_19") (pintype "bidirectional"))
      (node (ref "U2") (pin "8") (pinfunction "SDA_8") (pintype "bidirectional"))
    )
    (net (code "46") (name "SS") (class "Default")
      (node (ref "U$2") (pin "3") (pinfunction "~{CSN}_3") (pintype "bidirectional"))
      (node (ref "U1") (pin "8") (pinfunction "PB0(SS)_8") (pintype "bidirectional"))
    )
    (net (code "47") (name "UART_RX") (class "Default")
      (node (ref "U1") (pin "20") (pinfunction "PD2(RX)_20") (pintype "bidirectional"))
      (node (ref "UART_INTERFACE") (pin "1") (pinfunction "1_1") (pintype "passive"))
    )
    (net (code "48") (name "UART_TX") (class "Default")
      (node (ref "U1") (pin "21") (pinfunction "PD3(TX)_21") (pintype "bidirectional"))
      (node (ref "UART_INTERFACE") (pin "2") (pinfunction "2_2") (pintype "passive"))
    )
    (net (code "49") (name "VBAT") (class "Default")
      (node (ref "C5") (pin "2") (pinfunction "2_2") (pintype "passive"))
      (node (ref "IC1") (pin "3") (pinfunction "VBAT_3") (pintype "bidirectional"))
      (node (ref "J4") (pin "2") (pinfunction "2_2") (pintype "passive"))
      (node (ref "Q1") (pin "3") (pinfunction "D_3") (pintype "passive"))
      (node (ref "R14") (pin "1") (pinfunction "1_1") (pintype "passive"))
    )
    (net (code "50") (name "VBUS") (class "Default")
      (node (ref "C1") (pin "2") (pinfunction "2_2") (pintype "passive"))
      (node (ref "S1") (pin "2") (pinfunction "P_2") (pintype "passive"))
      (node (ref "U1") (pin "7") (pinfunction "VBUS_7") (pintype "bidirectional"))
      (node (ref "U4") (pin "1") (pinfunction "EN_1") (pintype "input"))
      (node (ref "U4") (pin "2") (pinfunction "IN_2") (pintype "power_in"))
    )
    (net (code "51") (name "VBUS_RAW") (class "Default")
      (node (ref "C4") (pin "2") (pinfunction "2_2") (pintype "passive"))
      (node (ref "CN1") (pin "VBUS") (pinfunction "VBUS_VBUS") (pintype "power_in"))
      (node (ref "D1") (pin "A") (pinfunction "A_A") (pintype "passive"))
      (node (ref "IC1") (pin "4") (pinfunction "VDD_4") (pintype "power_in"))
      (node (ref "LED2") (pin "A") (pinfunction "A_A") (pintype "passive"))
      (node (ref "Q1") (pin "1") (pinfunction "G_1") (pintype "passive"))
      (node (ref "R3") (pin "1") (pinfunction "1_1") (pintype "passive"))
      (node (ref "R8") (pin "1") (pinfunction "1_1") (pintype "passive"))
    )
    (net (code "52") (name "Y5_SDA") (class "Default")
      (node (ref "IC2") (pin "20") (pinfunction "COM0-SDA_20") (pintype "bidirectional"))
      (node (ref "IC3") (pin "5") (pinfunction "Y5_5") (pintype "bidirectional"))
    )
    (net (code "53") (name "unconnected-(CN1-PadID)") (class "Default")
      (node (ref "CN1") (pin "ID") (pinfunction "ID_ID") (pintype "bidirectional"))
    )
    (net (code "54") (name "unconnected-(IC2-PIN1-Pad1)") (class "Default")
      (node (ref "IC2") (pin "1") (pinfunction "PIN1_1") (pintype "no_connect"))
    )
    (net (code "55") (name "unconnected-(IC2-PIN7-Pad7)") (class "Default")
      (node (ref "IC2") (pin "7") (pinfunction "PIN7_7") (pintype "tri_state"))
    )
    (net (code "56") (name "unconnected-(IC2-PIN8-Pad8)") (class "Default")
      (node (ref "IC2") (pin "8") (pinfunction "PIN8_8") (pintype "tri_state"))
    )
    (net (code "57") (name "unconnected-(IC2-PIN12-Pad12)") (class "Default")
      (node (ref "IC2") (pin "12") (pinfunction "PIN12_12") (pintype "passive"))
    )
    (net (code "58") (name "unconnected-(IC2-PIN13-Pad13)") (class "Default")
      (node (ref "IC2") (pin "13") (pinfunction "PIN13_13") (pintype "passive"))
    )
    (net (code "59") (name "unconnected-(IC2-PIN21-Pad21)") (class "Default")
      (node (ref "IC2") (pin "21") (pinfunction "PIN21_21") (pintype "passive"))
    )
    (net (code "60") (name "unconnected-(IC2-PIN22-Pad22)") (class "Default")
      (node (ref "IC2") (pin "22") (pinfunction "PIN22_22") (pintype "passive"))
    )
    (net (code "61") (name "unconnected-(IC2-PIN23-Pad23)") (class "Default")
      (node (ref "IC2") (pin "23") (pinfunction "PIN23_23") (pintype "passive"))
    )
    (net (code "62") (name "unconnected-(IC2-PIN24-Pad24)") (class "Default")
      (node (ref "IC2") (pin "24") (pinfunction "PIN24_24") (pintype "passive"))
    )
    (net (code "63") (name "unconnected-(IC3-Y6-Pad2)") (class "Default")
      (node (ref "IC3") (pin "2") (pinfunction "Y6_2") (pintype "bidirectional"))
    )
    (net (code "64") (name "unconnected-(IC3-Y7-Pad4)") (class "Default")
      (node (ref "IC3") (pin "4") (pinfunction "Y7_4") (pintype "bidirectional"))
    )
    (net (code "65") (name "unconnected-(S1-O-Pad1)") (class "Default")
      (node (ref "S1") (pin "1") (pinfunction "O_1") (pintype "passive"))
    )
    (net (code "66") (name "unconnected-(U1-PB7-Pad12)") (class "Default")
      (node (ref "U1") (pin "12") (pinfunction "PB7_12") (pintype "bidirectional"))
    )
    (net (code "67") (name "unconnected-(U1-PD5-Pad22)") (class "Default")
      (node (ref "U1") (pin "22") (pinfunction "PD5_22") (pintype "bidirectional"))
    )
    (net (code "68") (name "unconnected-(U1-PF0(ADC0)-Pad41)") (class "Default")
      (node (ref "U1") (pin "41") (pinfunction "PF0(ADC0)_41") (pintype "bidirectional"))
    )
    (net (code "69") (name "unconnected-(U1-PF1(ADC1)-Pad40)") (class "Default")
      (node (ref "U1") (pin "40") (pinfunction "PF1(ADC1)_40") (pintype "bidirectional"))
    )
    (net (code "70") (name "unconnected-(U1-PF4(ADC4)-Pad39)") (class "Default")
      (node (ref "U1") (pin "39") (pinfunction "PF4(ADC4)_39") (pintype "bidirectional"))
    )
    (net (code "71") (name "unconnected-(U1-PF5(ADC5)-Pad38)") (class "Default")
      (node (ref "U1") (pin "38") (pinfunction "PF5(ADC5)_38") (pintype "bidirectional"))
    )
    (net (code "72") (name "unconnected-(U1-PF6(ADC6)-Pad37)") (class "Default")
      (node (ref "U1") (pin "37") (pinfunction "PF6(ADC6)_37") (pintype "bidirectional"))
    )
    (net (code "73") (name "unconnected-(U1-PF7(ADC7)-Pad36)") (class "Default")
      (node (ref "U1") (pin "36") (pinfunction "PF7(ADC7)_36") (pintype "bidirectional"))
    )
    (net (code "74") (name "unconnected-(U1-UVCC-Pad2)") (class "Default")
      (node (ref "U1") (pin "2") (pinfunction "UVCC_2") (pintype "bidirectional"))
    )
    (net (code "75") (name "~{HWB}") (class "Default")
      (node (ref "R16") (pin "2") (pinfunction "2_2") (pintype "passive"))
      (node (ref "SW2") (pin "1") (pinfunction "P_1") (pintype "passive"))
      (node (ref "SW2") (pin "3") (pinfunction "P1_3") (pintype "passive"))
      (node (ref "U1") (pin "33") (pinfunction "PE2/~{HWB}_33") (pintype "bidirectional"))
    )
    (net (code "76") (name "~{RESET}") (class "Default")
      (node (ref "J3") (pin "5") (pinfunction "5_5") (pintype "bidirectional"))
      (node (ref "R15") (pin "2") (pinfunction "2_2") (pintype "passive"))
      (node (ref "SW1") (pin "1") (pinfunction "P_1") (pintype "passive"))
      (node (ref "SW1") (pin "3") (pinfunction "P1_3") (pintype "passive"))
      (node (ref "U1") (pin "13") (pinfunction "~{RESET}_13") (pintype "bidirectional"))
    )
  )
)
